# chamber_biasa.net
KiCad netlist of a schematic drawn in EAGLE
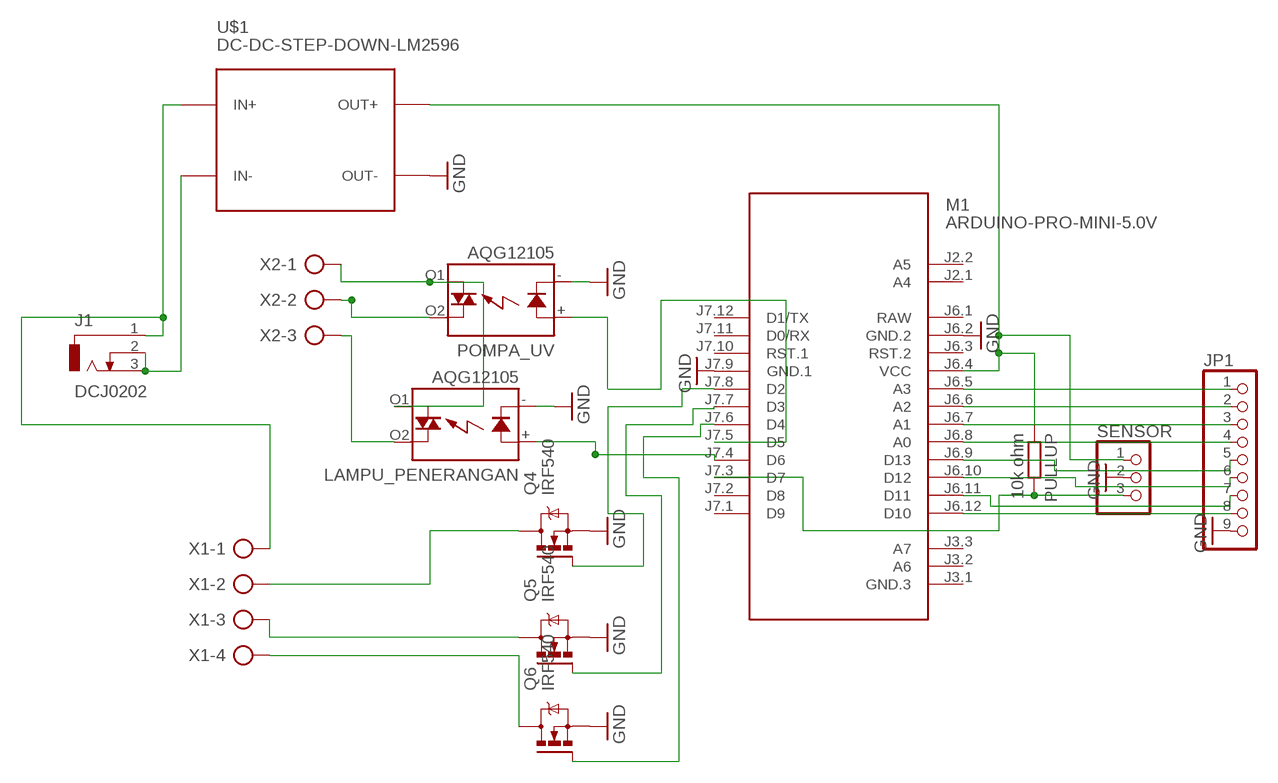
[diagram p0: schematic, sheet 1]

(export (version "E")
  (design (tool "Eeschema 10.0.6"))
  (components
    (comp (ref "J1")
      (value "DCJ0202")
      (footprint "eagle-import:DCJ0202")
      (libsource (lib "eagle-import") (part "DCJ0202"))
    )
    (comp (ref "JP1")
      (value "PINHD-1X9")
      (footprint "eagle-import:1X09")
      (libsource (lib "eagle-import") (part "PINHD-1X9"))
    )
    (comp (ref "LAMPU_PENERANGAN")
      (value "AQG12105")
      (footprint "eagle-import:AQG")
      (fields (field (name "MF") "AROMAT/ MATSUSHITA"))
      (libsource (lib "eagle-import") (part "AQG12105"))
    )
    (comp (ref "M1")
      (value "ARDUINO-PRO-MINI-5.0V")
      (footprint "eagle-import:ARDUINO-PRO-MINI")
      (libsource (lib "eagle-import") (part "ARDUINO-PRO-MINI-5.0V"))
    )
    (comp (ref "POMPA_UV")
      (value "AQG12105")
      (footprint "eagle-import:AQG")
      (fields (field (name "MF") "AROMAT/ MATSUSHITA"))
      (libsource (lib "eagle-import") (part "AQG12105"))
    )
    (comp (ref "PULLUP")
      (value "10k ohm")
      (footprint "eagle-import:0204_7")
      (libsource (lib "eagle-import") (part "R-EU_0204/7"))
    )
    (comp (ref "Q4")
      (value "IRF540")
      (footprint "eagle-import:TO220BV")
      (libsource (lib "eagle-import") (part "IRF540"))
    )
    (comp (ref "Q5")
      (value "IRF540")
      (footprint "eagle-import:TO220BV")
      (libsource (lib "eagle-import") (part "IRF540"))
    )
    (comp (ref "Q6")
      (value "IRF540")
      (footprint "eagle-import:TO220BV")
      (libsource (lib "eagle-import") (part "IRF540"))
    )
    (comp (ref "SENSOR")
      (value "PINHD-1X3")
      (footprint "eagle-import:1X03")
      (libsource (lib "eagle-import") (part "PINHD-1X3"))
    )
    (comp (ref "U$1")
      (value "DC-DC-STEP-DOWN-LM2596")
      (footprint "eagle-import:DC-DC-STEP-DOWN-LM2596")
      (libsource (lib "eagle-import") (part "DC-DC-STEP-DOWN-LM2596"))
    )
    (comp (ref "X1")
      (value "AK300/4")
      (footprint "eagle-import:AK300_4")
      (libsource (lib "eagle-import") (part "AK300/4"))
    )
    (comp (ref "X2")
      (value "AK300/3")
      (footprint "eagle-import:AK300_3")
      (libsource (lib "eagle-import") (part "AK300/3"))
    )
  )
  (nets
    (net (code "1") (name "/RAW") (class "Default")
      (node (ref "M1") (pin "J6.1") (pinfunction "RAW_J6.1") (pintype "power_in"))
    )
    (net (code "2") (name "GND") (class "Default")
      (node (ref "JP1") (pin "9") (pinfunction "9_9") (pintype "passive"))
      (node (ref "LAMPU_PENERANGAN") (pin "-") (pinfunction "K_-") (pintype "passive"))
      (node (ref "M1") (pin "J6.2") (pinfunction "GND.2_J6.2") (pintype "power_in"))
      (node (ref "M1") (pin "J7.9") (pinfunction "GND.1_J7.9") (pintype "power_in"))
      (node (ref "POMPA_UV") (pin "-") (pinfunction "K_-") (pintype "passive"))
      (node (ref "Q4") (pin "S") (pinfunction "S_S") (pintype "passive"))
      (node (ref "Q5") (pin "S") (pinfunction "S_S") (pintype "passive"))
      (node (ref "Q6") (pin "S") (pinfunction "S_S") (pintype "passive"))
      (node (ref "SENSOR") (pin "2") (pinfunction "2_2") (pintype "passive"))
      (node (ref "U$1") (pin "OUT-") (pinfunction "OUT-_OUT-") (pintype "bidirectional"))
    )
    (net (code "3") (name "Net-(J1-Pad2)") (class "Default")
      (node (ref "J1") (pin "2") (pinfunction "2_2") (pintype "passive"))
      (node (ref "J1") (pin "3") (pinfunction "3_3") (pintype "passive"))
      (node (ref "U$1") (pin "IN-") (pinfunction "IN-_IN-") (pintype "bidirectional"))
    )
    (net (code "4") (name "Net-(LAMPU_PENERANGAN-A)") (class "Default")
      (node (ref "LAMPU_PENERANGAN") (pin "+") (pinfunction "A_+") (pintype "passive"))
      (node (ref "M1") (pin "J7.4") (pinfunction "D6_J7.4") (pintype "bidirectional"))
    )
    (net (code "5") (name "Net-(LAMPU_PENERANGAN-DS1)") (class "Default")
      (node (ref "LAMPU_PENERANGAN") (pin "O2") (pinfunction "DS1_O2") (pintype "passive"))
      (node (ref "X2") (pin "3") (pinfunction "KL_3") (pintype "passive"))
    )
    (net (code "6") (name "Net-(LAMPU_PENERANGAN-DS2)") (class "Default")
      (node (ref "LAMPU_PENERANGAN") (pin "O1") (pinfunction "DS2_O1") (pintype "passive"))
      (node (ref "POMPA_UV") (pin "O1") (pinfunction "DS2_O1") (pintype "passive"))
      (node (ref "X2") (pin "1") (pinfunction "KL_1") (pintype "passive"))
    )
    (net (code "7") (name "Net-(M1-A0)") (class "Default")
      (node (ref "JP1") (pin "4") (pinfunction "4_4") (pintype "passive"))
      (node (ref "M1") (pin "J6.8") (pinfunction "A0_J6.8") (pintype "bidirectional"))
    )
    (net (code "8") (name "Net-(M1-A1)") (class "Default")
      (node (ref "JP1") (pin "3") (pinfunction "3_3") (pintype "passive"))
      (node (ref "M1") (pin "J6.7") (pinfunction "A1_J6.7") (pintype "bidirectional"))
    )
    (net (code "9") (name "Net-(M1-A2)") (class "Default")
      (node (ref "JP1") (pin "2") (pinfunction "2_2") (pintype "passive"))
      (node (ref "M1") (pin "J6.6") (pinfunction "A2_J6.6") (pintype "bidirectional"))
    )
    (net (code "10") (name "Net-(M1-A3)") (class "Default")
      (node (ref "JP1") (pin "1") (pinfunction "1_1") (pintype "passive"))
      (node (ref "M1") (pin "J6.5") (pinfunction "A3_J6.5") (pintype "bidirectional"))
    )
    (net (code "11") (name "Net-(M1-D2)") (class "Default")
      (node (ref "M1") (pin "J7.8") (pinfunction "D2_J7.8") (pintype "bidirectional"))
      (node (ref "Q4") (pin "G") (pinfunction "G_G") (pintype "passive"))
    )
    (net (code "12") (name "Net-(M1-D3)") (class "Default")
      (node (ref "M1") (pin "J7.7") (pinfunction "D3_J7.7") (pintype "bidirectional"))
      (node (ref "Q5") (pin "G") (pinfunction "G_G") (pintype "passive"))
    )
    (net (code "13") (name "Net-(M1-D4)") (class "Default")
      (node (ref "M1") (pin "J7.6") (pinfunction "D4_J7.6") (pintype "bidirectional"))
      (node (ref "Q6") (pin "G") (pinfunction "G_G") (pintype "passive"))
    )
    (net (code "14") (name "Net-(M1-D5)") (class "Default")
      (node (ref "M1") (pin "J7.5") (pinfunction "D5_J7.5") (pintype "bidirectional"))
      (node (ref "POMPA_UV") (pin "+") (pinfunction "A_+") (pintype "passive"))
    )
    (net (code "15") (name "Net-(M1-D7)") (class "Default")
      (node (ref "M1") (pin "J7.3") (pinfunction "D7_J7.3") (pintype "bidirectional"))
      (node (ref "PULLUP") (pin "2") (pinfunction "2_2") (pintype "passive"))
      (node (ref "SENSOR") (pin "3") (pinfunction "3_3") (pintype "passive"))
    )
    (net (code "16") (name "Net-(M1-D10)") (class "Default")
      (node (ref "JP1") (pin "8") (pinfunction "8_8") (pintype "passive"))
      (node (ref "M1") (pin "J6.12") (pinfunction "D10_J6.12") (pintype "bidirectional"))
    )
    (net (code "17") (name "Net-(M1-D11)") (class "Default")
      (node (ref "JP1") (pin "7") (pinfunction "7_7") (pintype "passive"))
      (node (ref "M1") (pin "J6.11") (pinfunction "D11_J6.11") (pintype "bidirectional"))
    )
    (net (code "18") (name "Net-(M1-D12)") (class "Default")
      (node (ref "JP1") (pin "6") (pinfunction "6_6") (pintype "passive"))
      (node (ref "M1") (pin "J6.10") (pinfunction "D12_J6.10") (pintype "bidirectional"))
    )
    (net (code "19") (name "Net-(M1-D13)") (class "Default")
      (node (ref "JP1") (pin "5") (pinfunction "5_5") (pintype "passive"))
      (node (ref "M1") (pin "J6.9") (pinfunction "D13_J6.9") (pintype "bidirectional"))
    )
    (net (code "20") (name "Net-(M1-VCC)") (class "Default")
      (node (ref "M1") (pin "J6.4") (pinfunction "VCC_J6.4") (pintype "power_in"))
      (node (ref "PULLUP") (pin "1") (pinfunction "1_1") (pintype "passive"))
      (node (ref "SENSOR") (pin "1") (pinfunction "1_1") (pintype "passive"))
      (node (ref "U$1") (pin "OUT+") (pinfunction "OUT+_OUT+") (pintype "bidirectional"))
    )
    (net (code "21") (name "Net-(POMPA_UV-DS1)") (class "Default")
      (node (ref "POMPA_UV") (pin "O2") (pinfunction "DS1_O2") (pintype "passive"))
      (node (ref "X2") (pin "2") (pinfunction "KL_2") (pintype "passive"))
    )
    (net (code "22") (name "Net-(X1A-KL)") (class "Default")
      (node (ref "J1") (pin "1") (pinfunction "1_1") (pintype "passive"))
      (node (ref "U$1") (pin "IN+") (pinfunction "IN+_IN+") (pintype "bidirectional"))
      (node (ref "X1") (pin "1") (pinfunction "KL_1") (pintype "passive"))
    )
    (net (code "23") (name "Net-(X1B-KL)") (class "Default")
      (node (ref "Q4") (pin "D") (pinfunction "D_D") (pintype "passive"))
      (node (ref "X1") (pin "2") (pinfunction "KL_2") (pintype "passive"))
    )
    (net (code "24") (name "Net-(X1C-KL)") (class "Default")
      (node (ref "Q5") (pin "D") (pinfunction "D_D") (pintype "passive"))
      (node (ref "X1") (pin "3") (pinfunction "KL_3") (pintype "passive"))
    )
    (net (code "25") (name "Net-(X1D-KL)") (class "Default")
      (node (ref "Q6") (pin "D") (pinfunction "D_D") (pintype "passive"))
      (node (ref "X1") (pin "4") (pinfunction "KL_4") (pintype "passive"))
    )
    (net (code "26") (name "unconnected-(M1-A4-PadJ2.1)") (class "Default")
      (node (ref "M1") (pin "J2.1") (pinfunction "A4_J2.1") (pintype "bidirectional"))
    )
    (net (code "27") (name "unconnected-(M1-A5-PadJ2.2)") (class "Default")
      (node (ref "M1") (pin "J2.2") (pinfunction "A5_J2.2") (pintype "bidirectional"))
    )
    (net (code "28") (name "unconnected-(M1-A6-PadJ3.2)") (class "Default")
      (node (ref "M1") (pin "J3.2") (pinfunction "A6_J3.2") (pintype "bidirectional"))
    )
    (net (code "29") (name "unconnected-(M1-A7-PadJ3.3)") (class "Default")
      (node (ref "M1") (pin "J3.3") (pinfunction "A7_J3.3") (pintype "bidirectional"))
    )
    (net (code "30") (name "unconnected-(M1-D0{slash}RX-PadJ7.11)") (class "Default")
      (node (ref "M1") (pin "J7.11") (pinfunction "D0/RX_J7.11") (pintype "bidirectional"))
    )
    (net (code "31") (name "unconnected-(M1-D1{slash}TX-PadJ7.12)") (class "Default")
      (node (ref "M1") (pin "J7.12") (pinfunction "D1/TX_J7.12") (pintype "bidirectional"))
    )
    (net (code "32") (name "unconnected-(M1-D8-PadJ7.2)") (class "Default")
      (node (ref "M1") (pin "J7.2") (pinfunction "D8_J7.2") (pintype "bidirectional"))
    )
    (net (code "33") (name "unconnected-(M1-D9-PadJ7.1)") (class "Default")
      (node (ref "M1") (pin "J7.1") (pinfunction "D9_J7.1") (pintype "bidirectional"))
    )
    (net (code "34") (name "unconnected-(M1-GND.3-PadJ3.1)") (class "Default")
      (node (ref "M1") (pin "J3.1") (pinfunction "GND.3_J3.1") (pintype "bidirectional"))
    )
    (net (code "35") (name "unconnected-(M1-RST.1-PadJ7.10)") (class "Default")
      (node (ref "M1") (pin "J7.10") (pinfunction "RST.1_J7.10") (pintype "bidirectional"))
    )
    (net (code "36") (name "unconnected-(M1-RST.2-PadJ6.3)") (class "Default")
      (node (ref "M1") (pin "J6.3") (pinfunction "RST.2_J6.3") (pintype "bidirectional"))
    )
  )
)
